# Power_Input.net
KiCad netlist of a schematic drawn in Altium Designer
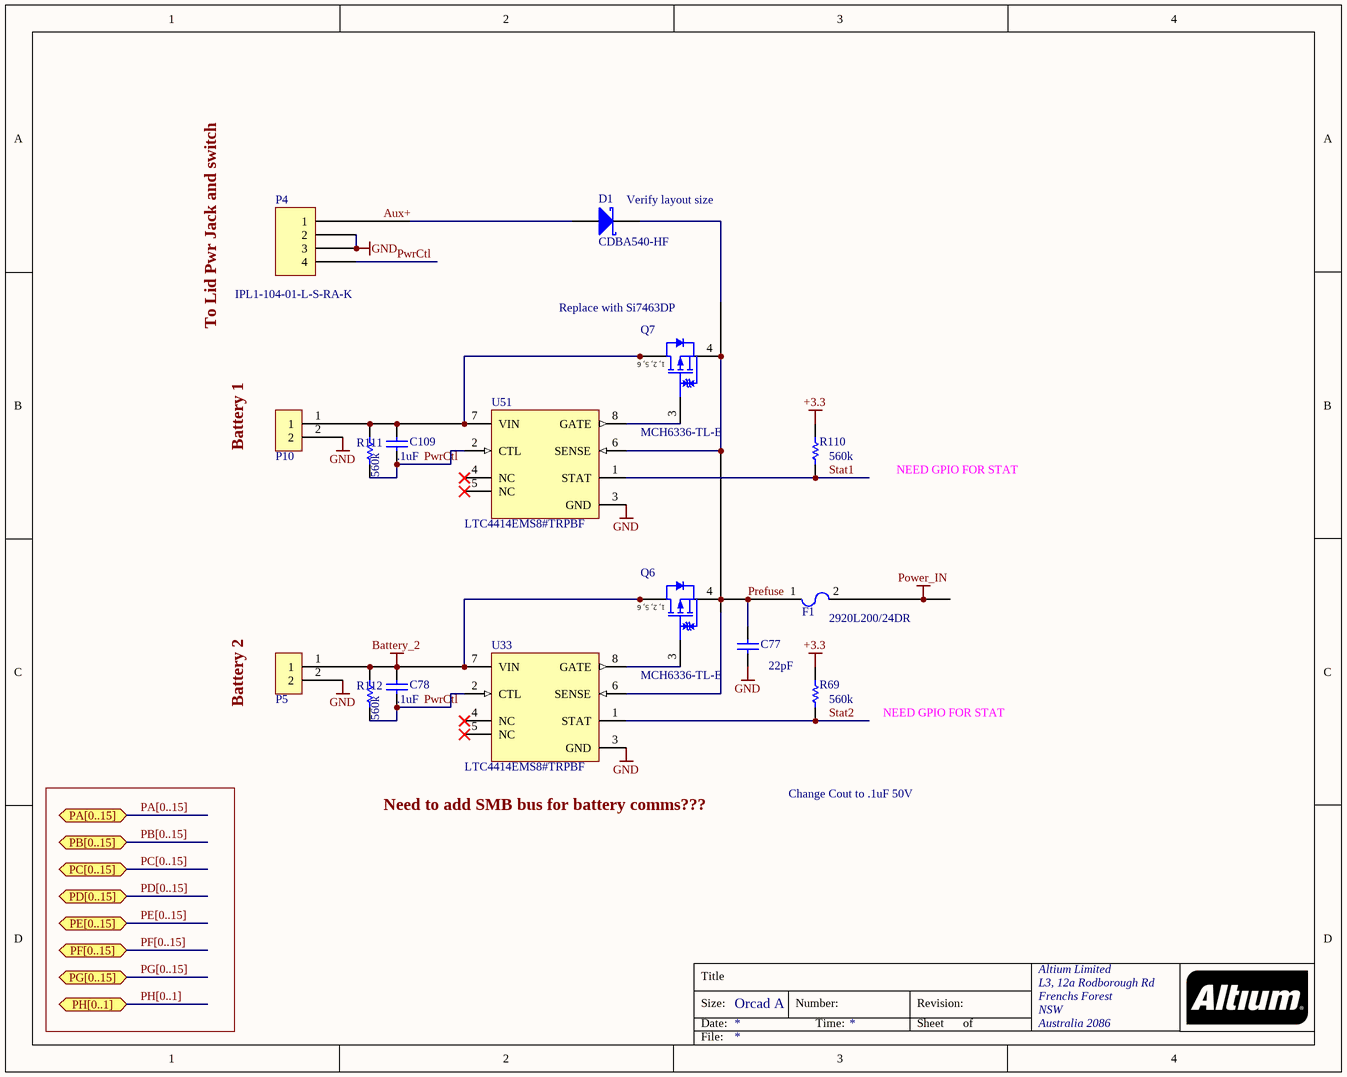
[diagram p0: Power_Input.SchDoc]

(export (version "E")
  (design (tool "Eeschema 10.0.6"))
  (components
    (comp (ref "C77")
      (value "CAP CER 10UF 6.3V X5R 1206")
      (footprint "CAPC1206(3216)130_N")
      (fields
        (field (name "MANUFACTURER") "Taiyo Yuden")
        (field (name "MANUFACTURER PART NUMBER") "JMK316BJ106ML-T")
        (field (name "TOLERANCE") "±20%")
        (field (name "CAPACITANCE") "22pF")
      )
      (libsource (lib "Altium Content Vault") (part "CMP-1037-04913-1"))
    )
    (comp (ref "C78")
      (value "CAP CER 10UF 6.3V X5R 1206")
      (footprint "CAPC1206(3216)130_N")
      (fields
        (field (name "MANUFACTURER") "Taiyo Yuden")
        (field (name "MANUFACTURER PART NUMBER") "JMK316BJ106ML-T")
        (field (name "TOLERANCE") "±20%")
        (field (name "CAPACITANCE") ".1uF")
      )
      (libsource (lib "Altium Content Vault") (part "CMP-1037-04913-1"))
    )
    (comp (ref "C109")
      (value "CAP CER 10UF 6.3V X5R 1206")
      (footprint "CAPC1206(3216)130_N")
      (fields
        (field (name "MANUFACTURER") "Taiyo Yuden")
        (field (name "MANUFACTURER PART NUMBER") "JMK316BJ106ML-T")
        (field (name "TOLERANCE") "±20%")
        (field (name "CAPACITANCE") ".1uF")
      )
      (libsource (lib "Altium Content Vault") (part "CMP-1037-04913-1"))
    )
    (comp (ref "D1")
      (value "CDBA540-HF")
      (footprint "VISH-DO-214AC-2_M")
      (description "DIODE SCHOTTKY 40V 5A DO214AB")
      (fields (field (name "MANUFACTURER") "Comchip Technology"))
      (libsource (lib "Miscellaneous Devices") (part "D Schottky"))
    )
    (comp (ref "F1")
      (value "PCT")
      (footprint "CAPC7451X12N")
      (libsource (lib "ZLS_Schematic_lib") (part "PCT"))
    )
    (comp (ref "P4")
      (value "IPL1-104-01-L-S-RA-K")
      (footprint "IPL1-104-01-L-S-RA-K")
      (fields
        (field (name "MANUFACTURER") "Samtec Inc.")
        (field (name "MANUFACTURER PART NUMBER") "IPL1-104-01-L-S-RA-K")
      )
      (libsource (lib "ZLS_Schematic_lib") (part "IPL1-104-01-L-S-RA-K"))
    )
    (comp (ref "P5")
      (value "IPL1-102-01-F-S-RA-K")
      (footprint "IPL1-102-01-F-S-RA-K")
      (libsource (lib "ZLS_Schematic_lib") (part "IPL1-102-01-F-S-RA-K"))
    )
    (comp (ref "P10")
      (value "IPL1-102-01-F-S-RA-K")
      (footprint "IPL1-102-01-F-S-RA-K")
      (libsource (lib "ZLS_Schematic_lib") (part "IPL1-102-01-F-S-RA-K"))
    )
    (comp (ref "Q6")
      (value "MCH6336-TL-E")
      (footprint "ONSC-MCPH-6_V")
      (description "P-Channel Power MOSFET, -12 V, -5 A, 43 mOhm, Single, 6-Pin MCPH, Pb-Free, Tape and Reel")
      (fields (field (name "MANUFACTURER") "On Semiconductor"))
      (libsource (lib "Altium Content Vault") (part "ONSC-PMOS-6_B"))
    )
    (comp (ref "Q7")
      (value "MCH6336-TL-E")
      (footprint "ONSC-MCPH-6_V")
      (description "P-Channel Power MOSFET, -12 V, -5 A, 43 mOhm, Single, 6-Pin MCPH, Pb-Free, Tape and Reel")
      (fields (field (name "MANUFACTURER") "On Semiconductor"))
      (libsource (lib "Altium Content Vault") (part "ONSC-PMOS-6_B"))
    )
    (comp (ref "R69")
      (value "560k")
      (footprint "RESC0402(1005)_L")
      (fields (field (name "TOLERANCE") "±1%"))
      (libsource (lib "Altium Content Vault") (part "CMP-1011-00927-1"))
    )
    (comp (ref "R110")
      (value "560k")
      (footprint "RESC0402(1005)_L")
      (fields (field (name "TOLERANCE") "±1%"))
      (libsource (lib "Altium Content Vault") (part "CMP-1011-00927-1"))
    )
    (comp (ref "R111")
      (value "560k")
      (footprint "RESC0402(1005)_L")
      (fields (field (name "TOLERANCE") "±1%"))
      (libsource (lib "Altium Content Vault") (part "CMP-1011-00927-1"))
    )
    (comp (ref "R112")
      (value "560k")
      (footprint "RESC0402(1005)_L")
      (fields (field (name "TOLERANCE") "±1%"))
      (libsource (lib "Altium Content Vault") (part "CMP-1011-00927-1"))
    )
    (comp (ref "U33")
      (value "LTC4414EMS8#TRPBF")
      (footprint "LT-MS8-8_L")
      (fields (field (name "MANUFACTURER") "Linear Technology"))
      (libsource (lib "Altium Content Vault") (part "CMP-0479-00214-1"))
    )
    (comp (ref "U51")
      (value "LTC4414EMS8#TRPBF")
      (footprint "LT-MS8-8_L")
      (fields (field (name "MANUFACTURER") "Linear Technology"))
      (libsource (lib "Altium Content Vault") (part "CMP-0479-00214-1"))
    )
  )
  (nets
    (net (code "115") (name "+3.3") (class "Default")
      (node (ref "R110") (pin "2") (pinfunction "2_2") (pintype "passive"))
      (node (ref "R69") (pin "2") (pinfunction "2_2") (pintype "passive"))
    )
    (net (code "116") (name "/Aux+") (class "Default")
      (node (ref "D1") (pin "1") (pinfunction "A_1") (pintype "passive"))
      (node (ref "P4") (pin "1") (pinfunction "1_1") (pintype "passive"))
    )
    (net (code "125") (name "/Prefuse") (class "Default")
      (node (ref "C77") (pin "2") (pinfunction "2_2") (pintype "passive"))
      (node (ref "D1") (pin "2") (pinfunction "K_2") (pintype "passive"))
      (node (ref "F1") (pin "1") (pinfunction "1_1") (pintype "passive"))
      (node (ref "Q6") (pin "4") (pinfunction "S_4") (pintype "passive"))
      (node (ref "Q7") (pin "4") (pinfunction "S_4") (pintype "passive"))
      (node (ref "U33") (pin "6") (pinfunction "SENSE_6") (pintype "input"))
      (node (ref "U51") (pin "6") (pinfunction "SENSE_6") (pintype "input"))
    )
    (net (code "126") (name "/PwrCtl") (class "Default")
      (node (ref "C109") (pin "1") (pinfunction "1_1") (pintype "passive"))
      (node (ref "C78") (pin "1") (pinfunction "1_1") (pintype "passive"))
      (node (ref "P4") (pin "4") (pinfunction "4_4") (pintype "passive"))
      (node (ref "R111") (pin "1") (pinfunction "1_1") (pintype "passive"))
      (node (ref "R112") (pin "1") (pinfunction "1_1") (pintype "passive"))
      (node (ref "U33") (pin "2") (pinfunction "CTL_2") (pintype "input"))
      (node (ref "U51") (pin "2") (pinfunction "CTL_2") (pintype "input"))
    )
    (net (code "127") (name "/Stat1") (class "Default")
      (node (ref "R110") (pin "1") (pinfunction "1_1") (pintype "passive"))
      (node (ref "U51") (pin "1") (pinfunction "STAT_1") (pintype "open_collector"))
    )
    (net (code "128") (name "/Stat2") (class "Default")
      (node (ref "R69") (pin "1") (pinfunction "1_1") (pintype "passive"))
      (node (ref "U33") (pin "1") (pinfunction "STAT_1") (pintype "open_collector"))
    )
    (net (code "129") (name "Battery_2") (class "Default")
      (node (ref "C78") (pin "2") (pinfunction "2_2") (pintype "passive"))
      (node (ref "P5") (pin "1") (pinfunction "1_1") (pintype "passive"))
      (node (ref "Q6") (pin "1") (pinfunction "D_1") (pintype "passive"))
      (node (ref "Q6") (pin "2") (pinfunction "D_2") (pintype "passive"))
      (node (ref "Q6") (pin "5") (pinfunction "D_5") (pintype "passive"))
      (node (ref "Q6") (pin "6") (pinfunction "D_6") (pintype "passive"))
      (node (ref "R112") (pin "2") (pinfunction "2_2") (pintype "passive"))
      (node (ref "U33") (pin "7") (pinfunction "VIN_7") (pintype "power_in"))
    )
    (net (code "130") (name "GND") (class "Default")
      (node (ref "C77") (pin "1") (pinfunction "1_1") (pintype "passive"))
      (node (ref "P10") (pin "2") (pinfunction "2_2") (pintype "passive"))
      (node (ref "P4") (pin "2") (pinfunction "2_2") (pintype "passive"))
      (node (ref "P4") (pin "3") (pinfunction "3_3") (pintype "passive"))
      (node (ref "P5") (pin "2") (pinfunction "2_2") (pintype "passive"))
      (node (ref "U33") (pin "3") (pinfunction "GND_3") (pintype "power_in"))
      (node (ref "U51") (pin "3") (pinfunction "GND_3") (pintype "power_in"))
    )
    (net (code "131") (name "Net-(Q6-G)") (class "Default")
      (node (ref "Q6") (pin "3") (pinfunction "G_3") (pintype "passive"))
      (node (ref "U33") (pin "8") (pinfunction "GATE_8") (pintype "output"))
    )
    (net (code "132") (name "Net-(Q7-G)") (class "Default")
      (node (ref "Q7") (pin "3") (pinfunction "G_3") (pintype "passive"))
      (node (ref "U51") (pin "8") (pinfunction "GATE_8") (pintype "output"))
    )
    (net (code "133") (name "Net-(U51-VIN)") (class "Default")
      (node (ref "C109") (pin "2") (pinfunction "2_2") (pintype "passive"))
      (node (ref "P10") (pin "1") (pinfunction "1_1") (pintype "passive"))
      (node (ref "Q7") (pin "1") (pinfunction "D_1") (pintype "passive"))
      (node (ref "Q7") (pin "2") (pinfunction "D_2") (pintype "passive"))
      (node (ref "Q7") (pin "5") (pinfunction "D_5") (pintype "passive"))
      (node (ref "Q7") (pin "6") (pinfunction "D_6") (pintype "passive"))
      (node (ref "R111") (pin "2") (pinfunction "2_2") (pintype "passive"))
      (node (ref "U51") (pin "7") (pinfunction "VIN_7") (pintype "power_in"))
    )
    (net (code "134") (name "Power_IN") (class "Default")
      (node (ref "F1") (pin "2") (pinfunction "2_2") (pintype "passive"))
    )
    (net (code "135") (name "unconnected-(U33-NC-Pad4)") (class "Default")
      (node (ref "U33") (pin "4") (pinfunction "NC_4") (pintype "passive+no_connect"))
    )
    (net (code "136") (name "unconnected-(U33-NC-Pad5)") (class "Default")
      (node (ref "U33") (pin "5") (pinfunction "NC_5") (pintype "passive+no_connect"))
    )
    (net (code "137") (name "unconnected-(U51-NC-Pad4)") (class "Default")
      (node (ref "U51") (pin "4") (pinfunction "NC_4") (pintype "passive+no_connect"))
    )
    (net (code "138") (name "unconnected-(U51-NC-Pad5)") (class "Default")
      (node (ref "U51") (pin "5") (pinfunction "NC_5") (pintype "passive+no_connect"))
    )
  )
)
